# FPGA.net
KiCad netlist of a schematic drawn in Altium Designer
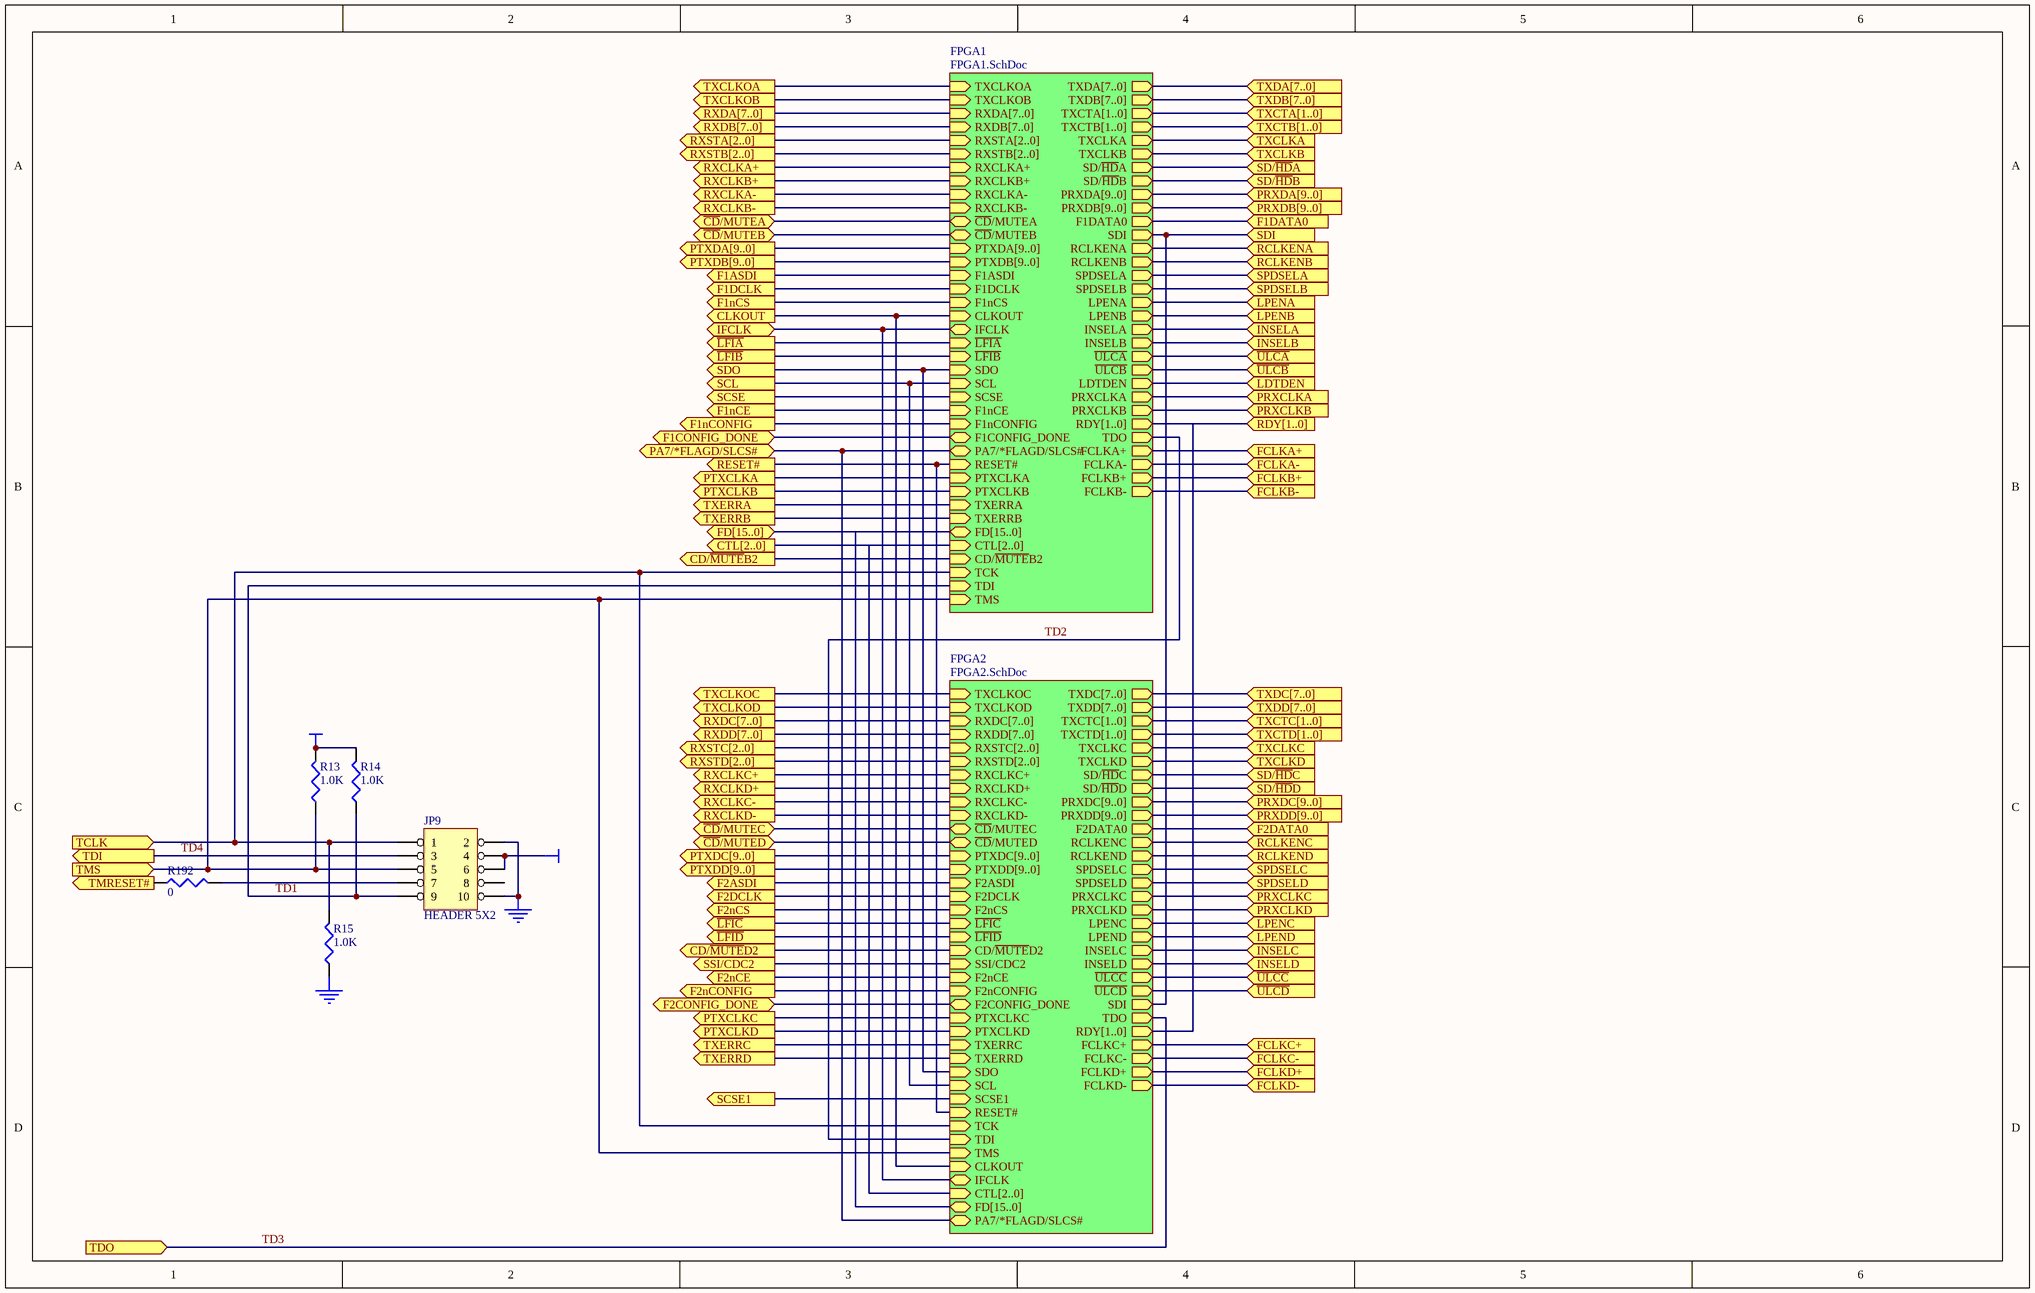
[diagram p0: FPGA.SchDoc]

(export (version "E")
  (design (tool "Eeschema 10.0.6"))
  (components
    (comp (ref "JP9") (value "~") (footprint "2X5PIN") (libsource (lib "Cypress Molson") (part "HEADER 5X2")))
    (comp (ref "R13") (value "1.0K") (footprint "0603") (libsource (lib "Cypress Molson") (part "RES1")))
    (comp (ref "R14") (value "1.0K") (footprint "0603") (libsource (lib "Cypress Molson") (part "RES1")))
    (comp (ref "R15") (value "1.0K") (footprint "0603") (libsource (lib "Cypress Molson") (part "RES1")))
    (comp (ref "R192") (value "0") (footprint "0603") (libsource (lib "Cypress Molson") (part "RES1")))
  )
  (nets
    (net (code "186") (name "+3.3V") (class "Default")
      (node (ref "JP9") (pin "4") (pinfunction "4_4") (pintype "passive"))
      (node (ref "JP9") (pin "6") (pinfunction "6_6") (pintype "passive"))
      (node (ref "R13") (pin "2") (pintype "passive"))
      (node (ref "R14") (pin "2") (pintype "passive"))
    )
    (net (code "280") (name "/TCLK") (class "Default")
      (node (ref "JP9") (pin "1") (pinfunction "1_1") (pintype "passive"))
      (node (ref "R15") (pin "2") (pintype "passive"))
    )
    (net (code "281") (name "/TD1") (class "Default")
      (node (ref "JP9") (pin "9") (pinfunction "9_9") (pintype "passive"))
      (node (ref "R14") (pin "1") (pintype "passive"))
    )
    (net (code "284") (name "/TD4") (class "Default")
      (node (ref "JP9") (pin "3") (pinfunction "3_3") (pintype "passive"))
    )
    (net (code "285") (name "/TMRESET#") (class "Default") (node (ref "R192") (pin "1") (pintype "passive")))
    (net (code "286") (name "/TMS") (class "Default")
      (node (ref "JP9") (pin "5") (pinfunction "5_5") (pintype "passive"))
      (node (ref "R13") (pin "1") (pintype "passive"))
    )
    (net (code "319") (name "GND") (class "Default")
      (node (ref "JP9") (pin "10") (pinfunction "10_10") (pintype "passive"))
      (node (ref "JP9") (pin "2") (pinfunction "2_2") (pintype "passive"))
      (node (ref "R15") (pin "1") (pintype "passive"))
    )
    (net (code "320") (name "Net-(JP9-Pad7)") (class "Default")
      (node (ref "JP9") (pin "7") (pinfunction "7_7") (pintype "passive"))
      (node (ref "R192") (pin "2") (pintype "passive"))
    )
    (net (code "321") (name "unconnected-(JP9-Pad8)") (class "Default")
      (node (ref "JP9") (pin "8") (pinfunction "8_8") (pintype "passive"))
    )
  )
)
